# 13_-LED_INDICATION.net
KiCad netlist of a schematic drawn in Altium Designer
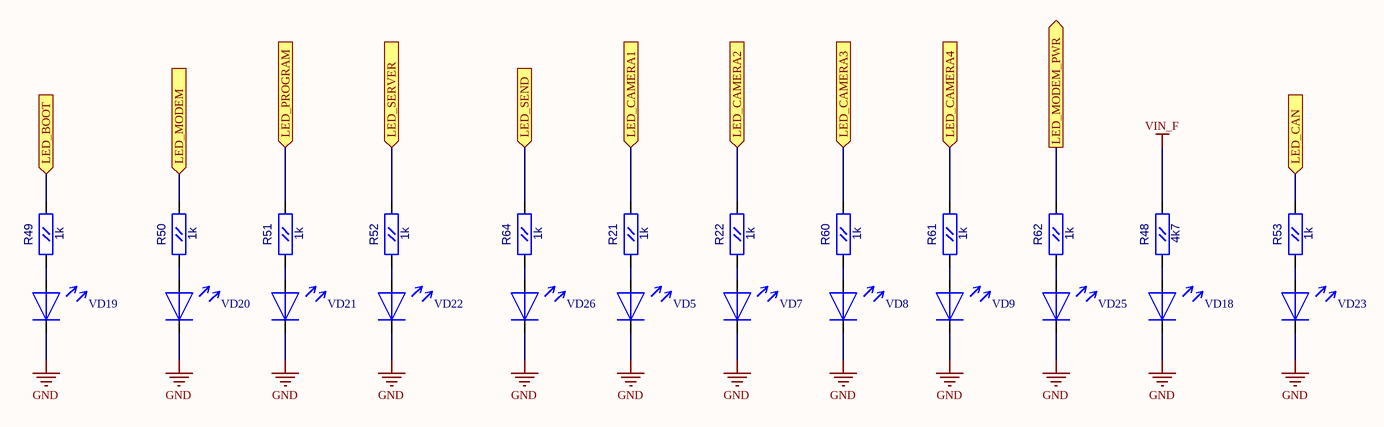
[diagram p0: [13]-LED_INDICATION.SchDoc]

(export (version "E")
  (design (tool "Eeschema 10.0.6"))
  (components
    (comp (ref "R21")
      (value "1k")
      (footprint "RC0603")
      (description "RC0603")
      (libsource (lib "gprs_modem_2") (part "RC0603"))
    )
    (comp (ref "R22")
      (value "1k")
      (footprint "RC0603")
      (description "RC0603")
      (libsource (lib "gprs_modem_2") (part "RC0603"))
    )
    (comp (ref "R48")
      (value "4k7")
      (footprint "RC0603")
      (description "RC0603")
      (libsource (lib "gprs_modem_2") (part "RC0603"))
    )
    (comp (ref "R49")
      (value "1k")
      (footprint "RC0603")
      (description "RC0603")
      (libsource (lib "gprs_modem_2") (part "RC0603"))
    )
    (comp (ref "R50")
      (value "1k")
      (footprint "RC0603")
      (description "RC0603")
      (libsource (lib "gprs_modem_2") (part "RC0603"))
    )
    (comp (ref "R51")
      (value "1k")
      (footprint "RC0603")
      (description "RC0603")
      (libsource (lib "gprs_modem_2") (part "RC0603"))
    )
    (comp (ref "R52")
      (value "1k")
      (footprint "RC0603")
      (description "RC0603")
      (libsource (lib "gprs_modem_2") (part "RC0603"))
    )
    (comp (ref "R53")
      (value "1k")
      (footprint "RC0603")
      (description "RC0603")
      (libsource (lib "gprs_modem_2") (part "RC0603"))
    )
    (comp (ref "R60")
      (value "1k")
      (footprint "RC0603")
      (description "RC0603")
      (libsource (lib "gprs_modem_2") (part "RC0603"))
    )
    (comp (ref "R61")
      (value "1k")
      (footprint "RC0603")
      (description "RC0603")
      (libsource (lib "gprs_modem_2") (part "RC0603"))
    )
    (comp (ref "R62")
      (value "1k")
      (footprint "RC0603")
      (description "RC0603")
      (libsource (lib "gprs_modem_2") (part "RC0603"))
    )
    (comp (ref "R64")
      (value "1k")
      (footprint "RC0603")
      (description "RC0603")
      (libsource (lib "gprs_modem_2") (part "RC0603"))
    )
    (comp (ref "VD5")
      (value "LED_0805")
      (footprint "LED0805")
      (libsource (lib "gprs_modem_2") (part "LED_0805"))
    )
    (comp (ref "VD7")
      (value "LED_0805")
      (footprint "LED0805")
      (libsource (lib "gprs_modem_2") (part "LED_0805"))
    )
    (comp (ref "VD8")
      (value "LED_0805")
      (footprint "LED0805")
      (libsource (lib "gprs_modem_2") (part "LED_0805"))
    )
    (comp (ref "VD9")
      (value "LED_0805")
      (footprint "LED0805")
      (libsource (lib "gprs_modem_2") (part "LED_0805"))
    )
    (comp (ref "VD18")
      (value "LED_0805")
      (footprint "LED0805")
      (libsource (lib "gprs_modem_2") (part "LED_0805"))
    )
    (comp (ref "VD19")
      (value "LED_0805")
      (footprint "LED0805")
      (libsource (lib "gprs_modem_2") (part "LED_0805"))
    )
    (comp (ref "VD20")
      (value "LED_0805")
      (footprint "LED0805")
      (libsource (lib "gprs_modem_2") (part "LED_0805"))
    )
    (comp (ref "VD21")
      (value "LED_0805")
      (footprint "LED0805")
      (libsource (lib "gprs_modem_2") (part "LED_0805"))
    )
    (comp (ref "VD22")
      (value "LED_0805")
      (footprint "LED0805")
      (libsource (lib "gprs_modem_2") (part "LED_0805"))
    )
    (comp (ref "VD23")
      (value "LED_0805")
      (footprint "LED0805")
      (libsource (lib "gprs_modem_2") (part "LED_0805"))
    )
    (comp (ref "VD25")
      (value "LED_0805")
      (footprint "LED0805")
      (libsource (lib "gprs_modem_2") (part "LED_0805"))
    )
    (comp (ref "VD26")
      (value "LED_0805")
      (footprint "LED0805")
      (libsource (lib "gprs_modem_2") (part "LED_0805"))
    )
  )
  (nets
    (net (code "1") (name "/LED_BOOT") (class "Default")
      (node (ref "R49") (pin "2") (pinfunction "B_2") (pintype "passive"))
    )
    (net (code "2") (name "/LED_CAMERA1") (class "Default")
      (node (ref "R21") (pin "2") (pinfunction "B_2") (pintype "passive"))
    )
    (net (code "3") (name "/LED_CAMERA2") (class "Default")
      (node (ref "R22") (pin "2") (pinfunction "B_2") (pintype "passive"))
    )
    (net (code "4") (name "/LED_CAMERA3") (class "Default")
      (node (ref "R60") (pin "2") (pinfunction "B_2") (pintype "passive"))
    )
    (net (code "5") (name "/LED_CAMERA4") (class "Default")
      (node (ref "R61") (pin "2") (pinfunction "B_2") (pintype "passive"))
    )
    (net (code "6") (name "/LED_CAN") (class "Default")
      (node (ref "R53") (pin "2") (pinfunction "B_2") (pintype "passive"))
    )
    (net (code "7") (name "/LED_MODEM") (class "Default")
      (node (ref "R50") (pin "2") (pinfunction "B_2") (pintype "passive"))
    )
    (net (code "8") (name "/LED_MODEM_PWR") (class "Default")
      (node (ref "R62") (pin "2") (pinfunction "B_2") (pintype "passive"))
    )
    (net (code "9") (name "/LED_PROGRAM") (class "Default")
      (node (ref "R51") (pin "2") (pinfunction "B_2") (pintype "passive"))
    )
    (net (code "10") (name "/LED_SEND") (class "Default")
      (node (ref "R64") (pin "2") (pinfunction "B_2") (pintype "passive"))
    )
    (net (code "11") (name "/LED_SERVER") (class "Default")
      (node (ref "R52") (pin "2") (pinfunction "B_2") (pintype "passive"))
    )
    (net (code "12") (name "GND") (class "Default")
      (node (ref "VD18") (pin "2") (pintype "passive"))
      (node (ref "VD19") (pin "2") (pintype "passive"))
      (node (ref "VD20") (pin "2") (pintype "passive"))
      (node (ref "VD21") (pin "2") (pintype "passive"))
      (node (ref "VD22") (pin "2") (pintype "passive"))
      (node (ref "VD23") (pin "2") (pintype "passive"))
      (node (ref "VD25") (pin "2") (pintype "passive"))
      (node (ref "VD26") (pin "2") (pintype "passive"))
      (node (ref "VD5") (pin "2") (pintype "passive"))
      (node (ref "VD7") (pin "2") (pintype "passive"))
      (node (ref "VD8") (pin "2") (pintype "passive"))
      (node (ref "VD9") (pin "2") (pintype "passive"))
    )
    (net (code "13") (name "Net-(R21-A)") (class "Default")
      (node (ref "R21") (pin "1") (pinfunction "A_1") (pintype "passive"))
      (node (ref "VD5") (pin "1") (pintype "passive"))
    )
    (net (code "14") (name "Net-(R22-A)") (class "Default")
      (node (ref "R22") (pin "1") (pinfunction "A_1") (pintype "passive"))
      (node (ref "VD7") (pin "1") (pintype "passive"))
    )
    (net (code "15") (name "Net-(R48-A)") (class "Default")
      (node (ref "R48") (pin "1") (pinfunction "A_1") (pintype "passive"))
      (node (ref "VD18") (pin "1") (pintype "passive"))
    )
    (net (code "16") (name "Net-(R49-A)") (class "Default")
      (node (ref "R49") (pin "1") (pinfunction "A_1") (pintype "passive"))
      (node (ref "VD19") (pin "1") (pintype "passive"))
    )
    (net (code "17") (name "Net-(R50-A)") (class "Default")
      (node (ref "R50") (pin "1") (pinfunction "A_1") (pintype "passive"))
      (node (ref "VD20") (pin "1") (pintype "passive"))
    )
    (net (code "18") (name "Net-(R51-A)") (class "Default")
      (node (ref "R51") (pin "1") (pinfunction "A_1") (pintype "passive"))
      (node (ref "VD21") (pin "1") (pintype "passive"))
    )
    (net (code "19") (name "Net-(R52-A)") (class "Default")
      (node (ref "R52") (pin "1") (pinfunction "A_1") (pintype "passive"))
      (node (ref "VD22") (pin "1") (pintype "passive"))
    )
    (net (code "20") (name "Net-(R53-A)") (class "Default")
      (node (ref "R53") (pin "1") (pinfunction "A_1") (pintype "passive"))
      (node (ref "VD23") (pin "1") (pintype "passive"))
    )
    (net (code "21") (name "Net-(R60-A)") (class "Default")
      (node (ref "R60") (pin "1") (pinfunction "A_1") (pintype "passive"))
      (node (ref "VD8") (pin "1") (pintype "passive"))
    )
    (net (code "22") (name "Net-(R61-A)") (class "Default")
      (node (ref "R61") (pin "1") (pinfunction "A_1") (pintype "passive"))
      (node (ref "VD9") (pin "1") (pintype "passive"))
    )
    (net (code "23") (name "Net-(R62-A)") (class "Default")
      (node (ref "R62") (pin "1") (pinfunction "A_1") (pintype "passive"))
      (node (ref "VD25") (pin "1") (pintype "passive"))
    )
    (net (code "24") (name "Net-(R64-A)") (class "Default")
      (node (ref "R64") (pin "1") (pinfunction "A_1") (pintype "passive"))
      (node (ref "VD26") (pin "1") (pintype "passive"))
    )
    (net (code "25") (name "VIN_F") (class "Default")
      (node (ref "R48") (pin "2") (pinfunction "B_2") (pintype "passive"))
    )
  )
)
